# Audio_Amplifier.net
KiCad netlist of a schematic drawn in Altium Designer
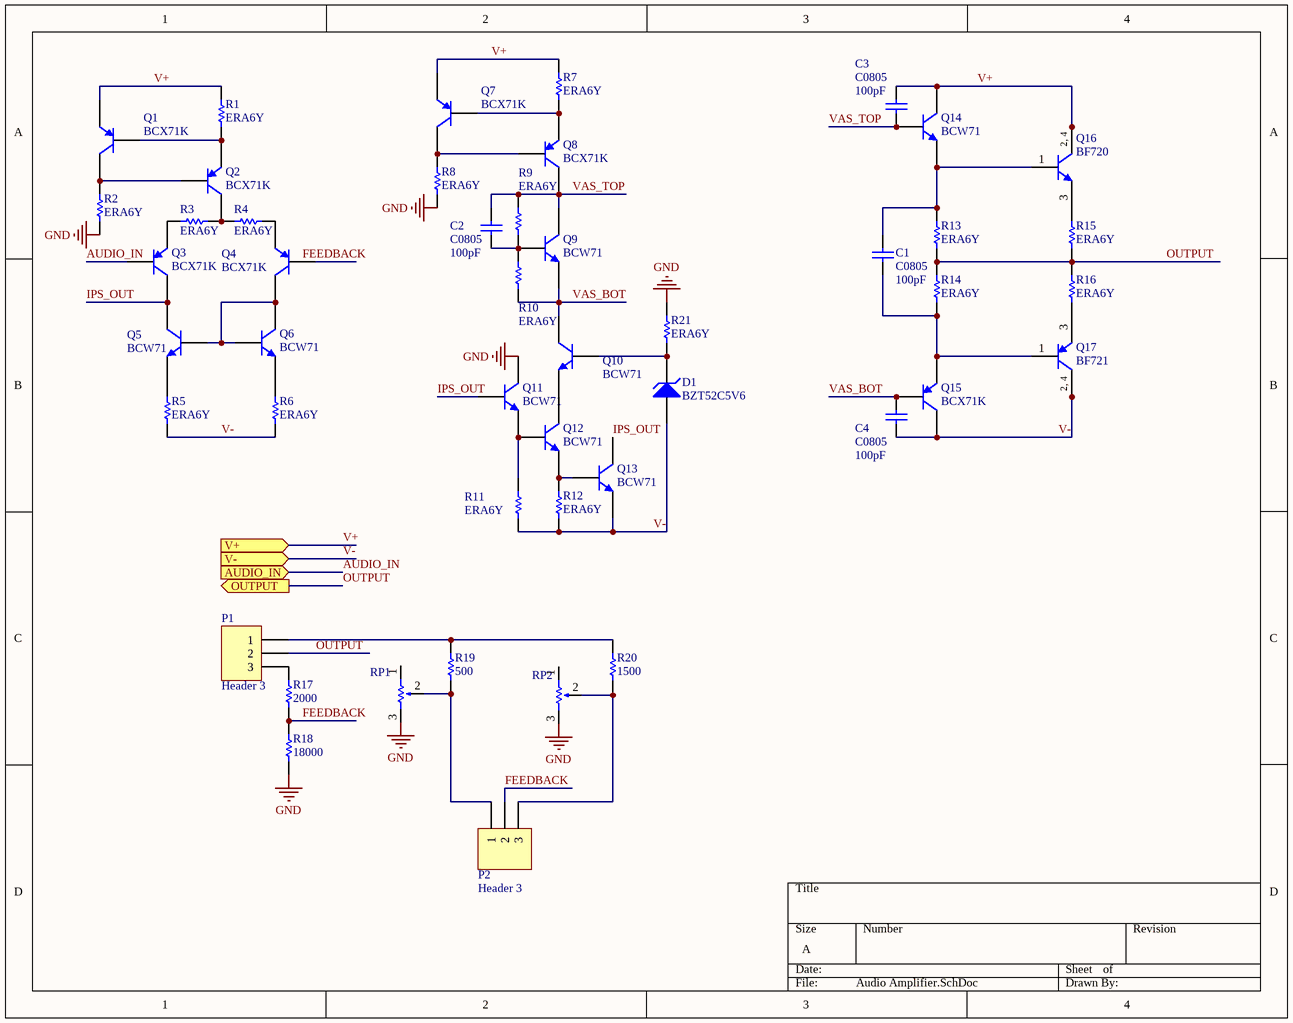
[diagram p0: Audio Amplifier.SchDoc]

(export (version "E")
  (design (tool "Eeschema 10.0.6"))
  (components
    (comp (ref "C1")
      (value "C0805")
      (footprint "0805")
      (description "Ceramic Chip Capacitor - Standard")
      (fields (field (name "ALTIUM_VALUE") "100pF") (field (name "PUBLISHER") "Altium Limited"))
      (libsource (lib "KEMET Chip Capacitor") (part "C0805"))
    )
    (comp (ref "C2")
      (value "C0805")
      (footprint "0805")
      (description "Ceramic Chip Capacitor - Standard")
      (fields (field (name "ALTIUM_VALUE") "100pF") (field (name "PUBLISHER") "Altium Limited"))
      (libsource (lib "KEMET Chip Capacitor") (part "C0805"))
    )
    (comp (ref "C3")
      (value "C0805")
      (footprint "0805")
      (description "Ceramic Chip Capacitor - Standard")
      (fields (field (name "ALTIUM_VALUE") "100pF") (field (name "PUBLISHER") "Altium Limited"))
      (libsource (lib "KEMET Chip Capacitor") (part "C0805"))
    )
    (comp (ref "C4")
      (value "C0805")
      (footprint "0805")
      (description "Ceramic Chip Capacitor - Standard")
      (fields (field (name "ALTIUM_VALUE") "100pF") (field (name "PUBLISHER") "Altium Limited"))
      (libsource (lib "KEMET Chip Capacitor") (part "C0805"))
    )
    (comp (ref "D1")
      (value "BZT52C5V6")
      (footprint "SOD-123")
      (description "Surface Mount Zener Diode")
      (fields (field (name "PUBLISHER") "Altium Limited"))
      (libsource (lib "Vishay Lite-On Discrete Diode") (part "BZT52C5V6"))
    )
    (comp (ref "P1")
      (value "Header 3")
      (footprint "HDR1X3")
      (description "Header, 3-Pin")
      (fields (field (name "PUBLISHER") "Altium Limited"))
      (libsource (lib "Miscellaneous Connectors") (part "Header 3"))
    )
    (comp (ref "P2")
      (value "Header 3")
      (footprint "HDR1X3")
      (description "Header, 3-Pin")
      (fields (field (name "PUBLISHER") "Altium Limited"))
      (libsource (lib "") (part "Header 3_1"))
    )
    (comp (ref "Q1")
      (value "BCX71K")
      (footprint "SOT-23B_N")
      (description "PNP Epitaxial Silicon Transistor")
      (fields (field (name "PUBLISHER") "Altium Limited"))
      (libsource (lib "FSC Discrete BJT") (part "BCX71K"))
    )
    (comp (ref "Q2")
      (value "BCX71K")
      (footprint "SOT-23B_N")
      (description "PNP Epitaxial Silicon Transistor")
      (fields (field (name "PUBLISHER") "Altium Limited"))
      (libsource (lib "FSC Discrete BJT") (part "BCX71K"))
    )
    (comp (ref "Q3")
      (value "BCX71K")
      (footprint "SOT-23B_N")
      (description "PNP Epitaxial Silicon Transistor")
      (fields (field (name "PUBLISHER") "Altium Limited"))
      (libsource (lib "FSC Discrete BJT") (part "BCX71K"))
    )
    (comp (ref "Q4")
      (value "BCX71K")
      (footprint "SOT-23B_N")
      (description "PNP Epitaxial Silicon Transistor")
      (fields (field (name "PUBLISHER") "Altium Limited"))
      (libsource (lib "FSC Discrete BJT") (part "BCX71K"))
    )
    (comp (ref "Q5")
      (value "BCW71")
      (footprint "SOT-23B_N")
      (description "NPN Epitaxial Silicon Transistor")
      (fields (field (name "PUBLISHER") "Altium Limited"))
      (libsource (lib "FSC Discrete BJT") (part "BCW71"))
    )
    (comp (ref "Q6")
      (value "BCW71")
      (footprint "SOT-23B_N")
      (description "NPN Epitaxial Silicon Transistor")
      (fields (field (name "PUBLISHER") "Altium Limited"))
      (libsource (lib "FSC Discrete BJT") (part "BCW71"))
    )
    (comp (ref "Q7")
      (value "BCX71K")
      (footprint "SOT-23B_N")
      (description "PNP Epitaxial Silicon Transistor")
      (fields (field (name "PUBLISHER") "Altium Limited"))
      (libsource (lib "FSC Discrete BJT") (part "BCX71K"))
    )
    (comp (ref "Q8")
      (value "BCX71K")
      (footprint "SOT-23B_N")
      (description "PNP Epitaxial Silicon Transistor")
      (fields (field (name "PUBLISHER") "Altium Limited"))
      (libsource (lib "FSC Discrete BJT") (part "BCX71K"))
    )
    (comp (ref "Q9")
      (value "BCW71")
      (footprint "SOT-23B_N")
      (description "NPN Epitaxial Silicon Transistor")
      (fields (field (name "PUBLISHER") "Altium Limited"))
      (libsource (lib "FSC Discrete BJT") (part "BCW71"))
    )
    (comp (ref "Q10")
      (value "BCW71")
      (footprint "SOT-23B_N")
      (description "NPN Epitaxial Silicon Transistor")
      (fields (field (name "PUBLISHER") "Altium Limited"))
      (libsource (lib "FSC Discrete BJT") (part "BCW71"))
    )
    (comp (ref "Q11")
      (value "BCW71")
      (footprint "SOT-23B_N")
      (description "NPN Epitaxial Silicon Transistor")
      (fields (field (name "PUBLISHER") "Altium Limited"))
      (libsource (lib "FSC Discrete BJT") (part "BCW71"))
    )
    (comp (ref "Q12")
      (value "BCW71")
      (footprint "SOT-23B_N")
      (description "NPN Epitaxial Silicon Transistor")
      (fields (field (name "PUBLISHER") "Altium Limited"))
      (libsource (lib "FSC Discrete BJT") (part "BCW71"))
    )
    (comp (ref "Q13")
      (value "BCW71")
      (footprint "SOT-23B_N")
      (description "NPN Epitaxial Silicon Transistor")
      (fields (field (name "PUBLISHER") "Altium Limited"))
      (libsource (lib "FSC Discrete BJT") (part "BCW71"))
    )
    (comp (ref "Q14")
      (value "BCW71")
      (footprint "SOT-23B_N")
      (description "NPN Epitaxial Silicon Transistor")
      (fields (field (name "PUBLISHER") "Altium Limited"))
      (libsource (lib "FSC Discrete BJT") (part "BCW71"))
    )
    (comp (ref "Q15")
      (value "BCX71K")
      (footprint "SOT-23B_N")
      (description "PNP Epitaxial Silicon Transistor")
      (fields (field (name "PUBLISHER") "Altium Limited"))
      (libsource (lib "FSC Discrete BJT") (part "BCX71K"))
    )
    (comp (ref "Q16")
      (value "BF720")
      (footprint "SOT-223")
      (description "NPN Silicon High-Voltage Transistor")
      (fields (field (name "PUBLISHER") "Altium Limited"))
      (libsource (lib "Infineon Discrete BJT") (part "BF720"))
    )
    (comp (ref "Q17")
      (value "BF721")
      (footprint "SOT-223")
      (description "PNP Silicon High-Voltage Transistor")
      (fields (field (name "PUBLISHER") "Altium Limited"))
      (libsource (lib "Infineon Discrete BJT") (part "BF721"))
    )
    (comp (ref "R1")
      (value "ERA6Y")
      (footprint "ERA-0805")
      (fields (field (name "PUBLISHER") "Altium Limited"))
      (libsource (lib "Panasonic Resistor") (part "ERA6Y"))
    )
    (comp (ref "R2")
      (value "ERA6Y")
      (footprint "ERA-0805")
      (fields (field (name "PUBLISHER") "Altium Limited"))
      (libsource (lib "Panasonic Resistor") (part "ERA6Y"))
    )
    (comp (ref "R3")
      (value "ERA6Y")
      (footprint "ERA-0805")
      (fields (field (name "PUBLISHER") "Altium Limited"))
      (libsource (lib "Panasonic Resistor") (part "ERA6Y"))
    )
    (comp (ref "R4")
      (value "ERA6Y")
      (footprint "ERA-0805")
      (fields (field (name "PUBLISHER") "Altium Limited"))
      (libsource (lib "Panasonic Resistor") (part "ERA6Y"))
    )
    (comp (ref "R5")
      (value "ERA6Y")
      (footprint "ERA-0805")
      (fields (field (name "PUBLISHER") "Altium Limited"))
      (libsource (lib "Panasonic Resistor") (part "ERA6Y"))
    )
    (comp (ref "R6")
      (value "ERA6Y")
      (footprint "ERA-0805")
      (fields (field (name "PUBLISHER") "Altium Limited"))
      (libsource (lib "Panasonic Resistor") (part "ERA6Y"))
    )
    (comp (ref "R7")
      (value "ERA6Y")
      (footprint "ERA-0805")
      (fields (field (name "PUBLISHER") "Altium Limited"))
      (libsource (lib "Panasonic Resistor") (part "ERA6Y"))
    )
    (comp (ref "R8")
      (value "ERA6Y")
      (footprint "ERA-0805")
      (fields (field (name "PUBLISHER") "Altium Limited"))
      (libsource (lib "Panasonic Resistor") (part "ERA6Y"))
    )
    (comp (ref "R9")
      (value "ERA6Y")
      (footprint "ERA-0805")
      (fields (field (name "PUBLISHER") "Altium Limited"))
      (libsource (lib "Panasonic Resistor") (part "ERA6Y"))
    )
    (comp (ref "R10")
      (value "ERA6Y")
      (footprint "ERA-0805")
      (fields (field (name "PUBLISHER") "Altium Limited"))
      (libsource (lib "Panasonic Resistor") (part "ERA6Y"))
    )
    (comp (ref "R11")
      (value "ERA6Y")
      (footprint "ERA-0805")
      (fields (field (name "PUBLISHER") "Altium Limited"))
      (libsource (lib "Panasonic Resistor") (part "ERA6Y"))
    )
    (comp (ref "R12")
      (value "ERA6Y")
      (footprint "ERA-0805")
      (fields (field (name "PUBLISHER") "Altium Limited"))
      (libsource (lib "Panasonic Resistor") (part "ERA6Y"))
    )
    (comp (ref "R13")
      (value "ERA6Y")
      (footprint "ERA-0805")
      (fields (field (name "PUBLISHER") "Altium Limited"))
      (libsource (lib "Panasonic Resistor") (part "ERA6Y"))
    )
    (comp (ref "R14")
      (value "ERA6Y")
      (footprint "ERA-0805")
      (fields (field (name "PUBLISHER") "Altium Limited"))
      (libsource (lib "Panasonic Resistor") (part "ERA6Y"))
    )
    (comp (ref "R15")
      (value "ERA6Y")
      (footprint "ERA-0805")
      (fields (field (name "PUBLISHER") "Altium Limited"))
      (libsource (lib "Panasonic Resistor") (part "ERA6Y"))
    )
    (comp (ref "R16")
      (value "ERA6Y")
      (footprint "ERA-0805")
      (fields (field (name "PUBLISHER") "Altium Limited"))
      (libsource (lib "Panasonic Resistor") (part "ERA6Y"))
    )
    (comp (ref "R17")
      (value "2000")
      (footprint "ERA-0805")
      (fields (field (name "PUBLISHER") "Altium Limited"))
      (libsource (lib "Panasonic Resistor") (part "ERA6Y"))
    )
    (comp (ref "R18")
      (value "18000")
      (footprint "ERA-0805")
      (fields (field (name "PUBLISHER") "Altium Limited"))
      (libsource (lib "Panasonic Resistor") (part "ERA6Y"))
    )
    (comp (ref "R19")
      (value "500")
      (footprint "ERA-0805")
      (fields (field (name "PUBLISHER") "Altium Limited"))
      (libsource (lib "Panasonic Resistor") (part "ERA6Y"))
    )
    (comp (ref "R20")
      (value "1500")
      (footprint "ERA-0805")
      (fields (field (name "PUBLISHER") "Altium Limited"))
      (libsource (lib "Panasonic Resistor") (part "ERA6Y"))
    )
    (comp (ref "R21")
      (value "ERA6Y")
      (footprint "ERA-0805")
      (fields (field (name "PUBLISHER") "Altium Limited"))
      (libsource (lib "Panasonic Resistor") (part "ERA6Y"))
    )
    (comp (ref "RP1")
      (value "Panasonic Potentiometer")
      (footprint "Panasonic Potentiometer")
      (libsource (lib "Custom Parts") (part "Panasonic Potentiometer"))
    )
    (comp (ref "RP2")
      (value "Panasonic Potentiometer")
      (footprint "Panasonic Potentiometer")
      (libsource (lib "Custom Parts") (part "Panasonic Potentiometer"))
    )
  )
  (nets
    (net (code "1") (name "/AUDIO_IN") (class "Default")
      (node (ref "Q3") (pin "1") (pinfunction "B_1") (pintype "passive"))
    )
    (net (code "2") (name "/FEEDBACK") (class "Default")
      (node (ref "P2") (pin "2") (pinfunction "2_2") (pintype "passive"))
      (node (ref "R17") (pin "1") (pinfunction "1_1") (pintype "passive"))
      (node (ref "R18") (pin "2") (pinfunction "2_2") (pintype "passive"))
    )
    (net (code "3") (name "/IPS_OUT") (class "Default")
      (node (ref "Q11") (pin "1") (pinfunction "B_1") (pintype "passive"))
      (node (ref "Q13") (pin "3") (pinfunction "C_3") (pintype "passive"))
      (node (ref "Q3") (pin "3") (pinfunction "C_3") (pintype "passive"))
      (node (ref "Q5") (pin "3") (pinfunction "C_3") (pintype "passive"))
    )
    (net (code "4") (name "/OUTPUT") (class "Default")
      (node (ref "P1") (pin "2") (pinfunction "2_2") (pintype "passive"))
      (node (ref "R13") (pin "1") (pinfunction "1_1") (pintype "passive"))
      (node (ref "R14") (pin "2") (pinfunction "2_2") (pintype "passive"))
      (node (ref "R15") (pin "1") (pinfunction "1_1") (pintype "passive"))
      (node (ref "R16") (pin "2") (pinfunction "2_2") (pintype "passive"))
    )
    (net (code "5") (name "/V+") (class "Default")
      (node (ref "C3") (pin "2") (pinfunction "2_2") (pintype "passive"))
      (node (ref "Q1") (pin "2") (pinfunction "E_2") (pintype "passive"))
      (node (ref "Q14") (pin "3") (pinfunction "C_3") (pintype "passive"))
      (node (ref "Q16") (pin "2") (pinfunction "C_2") (pintype "passive"))
      (node (ref "Q16") (pin "4") (pinfunction "C_4") (pintype "passive"))
      (node (ref "Q7") (pin "2") (pinfunction "E_2") (pintype "passive"))
      (node (ref "R1") (pin "2") (pinfunction "2_2") (pintype "passive"))
      (node (ref "R7") (pin "2") (pinfunction "2_2") (pintype "passive"))
    )
    (net (code "6") (name "/V-") (class "Default")
      (node (ref "C4") (pin "1") (pinfunction "1_1") (pintype "passive"))
      (node (ref "D1") (pin "1") (pinfunction "A_1") (pintype "passive"))
      (node (ref "Q13") (pin "2") (pinfunction "E_2") (pintype "passive"))
      (node (ref "Q15") (pin "3") (pinfunction "C_3") (pintype "passive"))
      (node (ref "Q17") (pin "2") (pinfunction "C_2") (pintype "passive"))
      (node (ref "Q17") (pin "4") (pinfunction "C_4") (pintype "passive"))
      (node (ref "R11") (pin "1") (pinfunction "1_1") (pintype "passive"))
      (node (ref "R12") (pin "1") (pinfunction "1_1") (pintype "passive"))
      (node (ref "R5") (pin "2") (pinfunction "2_2") (pintype "passive"))
      (node (ref "R6") (pin "2") (pinfunction "2_2") (pintype "passive"))
    )
    (net (code "7") (name "/VAS_BOT") (class "Default")
      (node (ref "C4") (pin "2") (pinfunction "2_2") (pintype "passive"))
      (node (ref "Q10") (pin "3") (pinfunction "C_3") (pintype "passive"))
      (node (ref "Q15") (pin "1") (pinfunction "B_1") (pintype "passive"))
      (node (ref "Q9") (pin "2") (pinfunction "E_2") (pintype "passive"))
      (node (ref "R9") (pin "1") (pinfunction "1_1") (pintype "passive"))
    )
    (net (code "8") (name "/VAS_TOP") (class "Default")
      (node (ref "C2") (pin "2") (pinfunction "2_2") (pintype "passive"))
      (node (ref "C3") (pin "1") (pinfunction "1_1") (pintype "passive"))
      (node (ref "Q14") (pin "1") (pinfunction "B_1") (pintype "passive"))
      (node (ref "Q8") (pin "3") (pinfunction "C_3") (pintype "passive"))
      (node (ref "Q9") (pin "3") (pinfunction "C_3") (pintype "passive"))
      (node (ref "R10") (pin "2") (pinfunction "2_2") (pintype "passive"))
    )
    (net (code "9") (name "GND") (class "Default")
      (node (ref "Q11") (pin "3") (pinfunction "C_3") (pintype "passive"))
      (node (ref "R18") (pin "1") (pinfunction "1_1") (pintype "passive"))
      (node (ref "R2") (pin "1") (pinfunction "1_1") (pintype "passive"))
      (node (ref "R21") (pin "2") (pinfunction "2_2") (pintype "passive"))
      (node (ref "R8") (pin "1") (pinfunction "1_1") (pintype "passive"))
      (node (ref "RP1") (pin "3") (pinfunction "3_3") (pintype "passive"))
      (node (ref "RP2") (pin "3") (pinfunction "3_3") (pintype "passive"))
    )
    (net (code "10") (name "Net-(D1-K)") (class "Default")
      (node (ref "D1") (pin "2") (pinfunction "K_2") (pintype "passive"))
      (node (ref "Q10") (pin "1") (pinfunction "B_1") (pintype "passive"))
      (node (ref "R21") (pin "1") (pinfunction "1_1") (pintype "passive"))
    )
    (net (code "11") (name "Net-(P1-Pad1)") (class "Default")
      (node (ref "P1") (pin "1") (pinfunction "1_1") (pintype "passive"))
      (node (ref "R19") (pin "2") (pinfunction "2_2") (pintype "passive"))
      (node (ref "R20") (pin "2") (pinfunction "2_2") (pintype "passive"))
    )
    (net (code "12") (name "Net-(P1-Pad3)") (class "Default")
      (node (ref "P1") (pin "3") (pinfunction "3_3") (pintype "passive"))
      (node (ref "R17") (pin "2") (pinfunction "2_2") (pintype "passive"))
    )
    (net (code "13") (name "Net-(P2-Pad1)") (class "Default")
      (node (ref "P2") (pin "1") (pinfunction "1_1") (pintype "passive"))
      (node (ref "R19") (pin "1") (pinfunction "1_1") (pintype "passive"))
      (node (ref "RP1") (pin "2") (pinfunction "2_2") (pintype "passive"))
    )
    (net (code "14") (name "Net-(P2-Pad3)") (class "Default")
      (node (ref "P2") (pin "3") (pinfunction "3_3") (pintype "passive"))
      (node (ref "R20") (pin "1") (pinfunction "1_1") (pintype "passive"))
      (node (ref "RP2") (pin "2") (pinfunction "2_2") (pintype "passive"))
    )
    (net (code "15") (name "Net-(Q1-B)") (class "Default")
      (node (ref "Q1") (pin "1") (pinfunction "B_1") (pintype "passive"))
      (node (ref "Q2") (pin "2") (pinfunction "E_2") (pintype "passive"))
      (node (ref "R1") (pin "1") (pinfunction "1_1") (pintype "passive"))
    )
    (net (code "16") (name "Net-(Q1-C)") (class "Default")
      (node (ref "Q1") (pin "3") (pinfunction "C_3") (pintype "passive"))
      (node (ref "Q2") (pin "1") (pinfunction "B_1") (pintype "passive"))
      (node (ref "R2") (pin "2") (pinfunction "2_2") (pintype "passive"))
    )
    (net (code "17") (name "Net-(Q2-C)") (class "Default")
      (node (ref "Q2") (pin "3") (pinfunction "C_3") (pintype "passive"))
      (node (ref "R3") (pin "1") (pinfunction "1_1") (pintype "passive"))
      (node (ref "R4") (pin "2") (pinfunction "2_2") (pintype "passive"))
    )
    (net (code "18") (name "Net-(Q3-E)") (class "Default")
      (node (ref "Q3") (pin "2") (pinfunction "E_2") (pintype "passive"))
      (node (ref "R3") (pin "2") (pinfunction "2_2") (pintype "passive"))
    )
    (net (code "19") (name "Net-(Q4-C)") (class "Default")
      (node (ref "Q4") (pin "3") (pinfunction "C_3") (pintype "passive"))
      (node (ref "Q5") (pin "1") (pinfunction "B_1") (pintype "passive"))
      (node (ref "Q6") (pin "1") (pinfunction "B_1") (pintype "passive"))
      (node (ref "Q6") (pin "3") (pinfunction "C_3") (pintype "passive"))
    )
    (net (code "20") (name "Net-(Q4-E)") (class "Default")
      (node (ref "Q4") (pin "2") (pinfunction "E_2") (pintype "passive"))
      (node (ref "R4") (pin "1") (pinfunction "1_1") (pintype "passive"))
    )
    (net (code "21") (name "Net-(Q5-E)") (class "Default")
      (node (ref "Q5") (pin "2") (pinfunction "E_2") (pintype "passive"))
      (node (ref "R5") (pin "1") (pinfunction "1_1") (pintype "passive"))
    )
    (net (code "22") (name "Net-(Q6-E)") (class "Default")
      (node (ref "Q6") (pin "2") (pinfunction "E_2") (pintype "passive"))
      (node (ref "R6") (pin "1") (pinfunction "1_1") (pintype "passive"))
    )
    (net (code "23") (name "Net-(Q7-B)") (class "Default")
      (node (ref "Q7") (pin "1") (pinfunction "B_1") (pintype "passive"))
      (node (ref "Q8") (pin "2") (pinfunction "E_2") (pintype "passive"))
      (node (ref "R7") (pin "1") (pinfunction "1_1") (pintype "passive"))
    )
    (net (code "24") (name "Net-(Q7-C)") (class "Default")
      (node (ref "Q7") (pin "3") (pinfunction "C_3") (pintype "passive"))
      (node (ref "Q8") (pin "1") (pinfunction "B_1") (pintype "passive"))
      (node (ref "R8") (pin "2") (pinfunction "2_2") (pintype "passive"))
    )
    (net (code "25") (name "Net-(Q9-B)") (class "Default")
      (node (ref "C2") (pin "1") (pinfunction "1_1") (pintype "passive"))
      (node (ref "Q9") (pin "1") (pinfunction "B_1") (pintype "passive"))
      (node (ref "R10") (pin "1") (pinfunction "1_1") (pintype "passive"))
      (node (ref "R9") (pin "2") (pinfunction "2_2") (pintype "passive"))
    )
    (net (code "26") (name "Net-(Q10-E)") (class "Default")
      (node (ref "Q10") (pin "2") (pinfunction "E_2") (pintype "passive"))
      (node (ref "Q12") (pin "3") (pinfunction "C_3") (pintype "passive"))
    )
    (net (code "27") (name "Net-(Q11-E)") (class "Default")
      (node (ref "Q11") (pin "2") (pinfunction "E_2") (pintype "passive"))
      (node (ref "Q12") (pin "1") (pinfunction "B_1") (pintype "passive"))
      (node (ref "R11") (pin "2") (pinfunction "2_2") (pintype "passive"))
    )
    (net (code "28") (name "Net-(Q12-E)") (class "Default")
      (node (ref "Q12") (pin "2") (pinfunction "E_2") (pintype "passive"))
      (node (ref "Q13") (pin "1") (pinfunction "B_1") (pintype "passive"))
      (node (ref "R12") (pin "2") (pinfunction "2_2") (pintype "passive"))
    )
    (net (code "29") (name "Net-(Q14-E)") (class "Default")
      (node (ref "C1") (pin "2") (pinfunction "2_2") (pintype "passive"))
      (node (ref "Q14") (pin "2") (pinfunction "E_2") (pintype "passive"))
      (node (ref "Q16") (pin "1") (pinfunction "B_1") (pintype "passive"))
      (node (ref "R13") (pin "2") (pinfunction "2_2") (pintype "passive"))
    )
    (net (code "30") (name "Net-(Q15-E)") (class "Default")
      (node (ref "C1") (pin "1") (pinfunction "1_1") (pintype "passive"))
      (node (ref "Q15") (pin "2") (pinfunction "E_2") (pintype "passive"))
      (node (ref "Q17") (pin "1") (pinfunction "B_1") (pintype "passive"))
      (node (ref "R14") (pin "1") (pinfunction "1_1") (pintype "passive"))
    )
    (net (code "31") (name "Net-(Q16-E)") (class "Default")
      (node (ref "Q16") (pin "3") (pinfunction "E_3") (pintype "passive"))
      (node (ref "R15") (pin "2") (pinfunction "2_2") (pintype "passive"))
    )
    (net (code "32") (name "Net-(Q17-E)") (class "Default")
      (node (ref "Q17") (pin "3") (pinfunction "E_3") (pintype "passive"))
      (node (ref "R16") (pin "1") (pinfunction "1_1") (pintype "passive"))
    )
    (net (code "33") (name "unconnected-(Q4-B-Pad1)") (class "Default")
      (node (ref "Q4") (pin "1") (pinfunction "B_1") (pintype "passive"))
    )
    (net (code "34") (name "unconnected-(RP1-Pad1)") (class "Default")
      (node (ref "RP1") (pin "1") (pinfunction "1_1") (pintype "passive"))
    )
    (net (code "35") (name "unconnected-(RP2-Pad1)") (class "Default")
      (node (ref "RP2") (pin "1") (pinfunction "1_1") (pintype "passive"))
    )
  )
)
